# plugV9.net
KiCad netlist of a schematic drawn in EAGLE
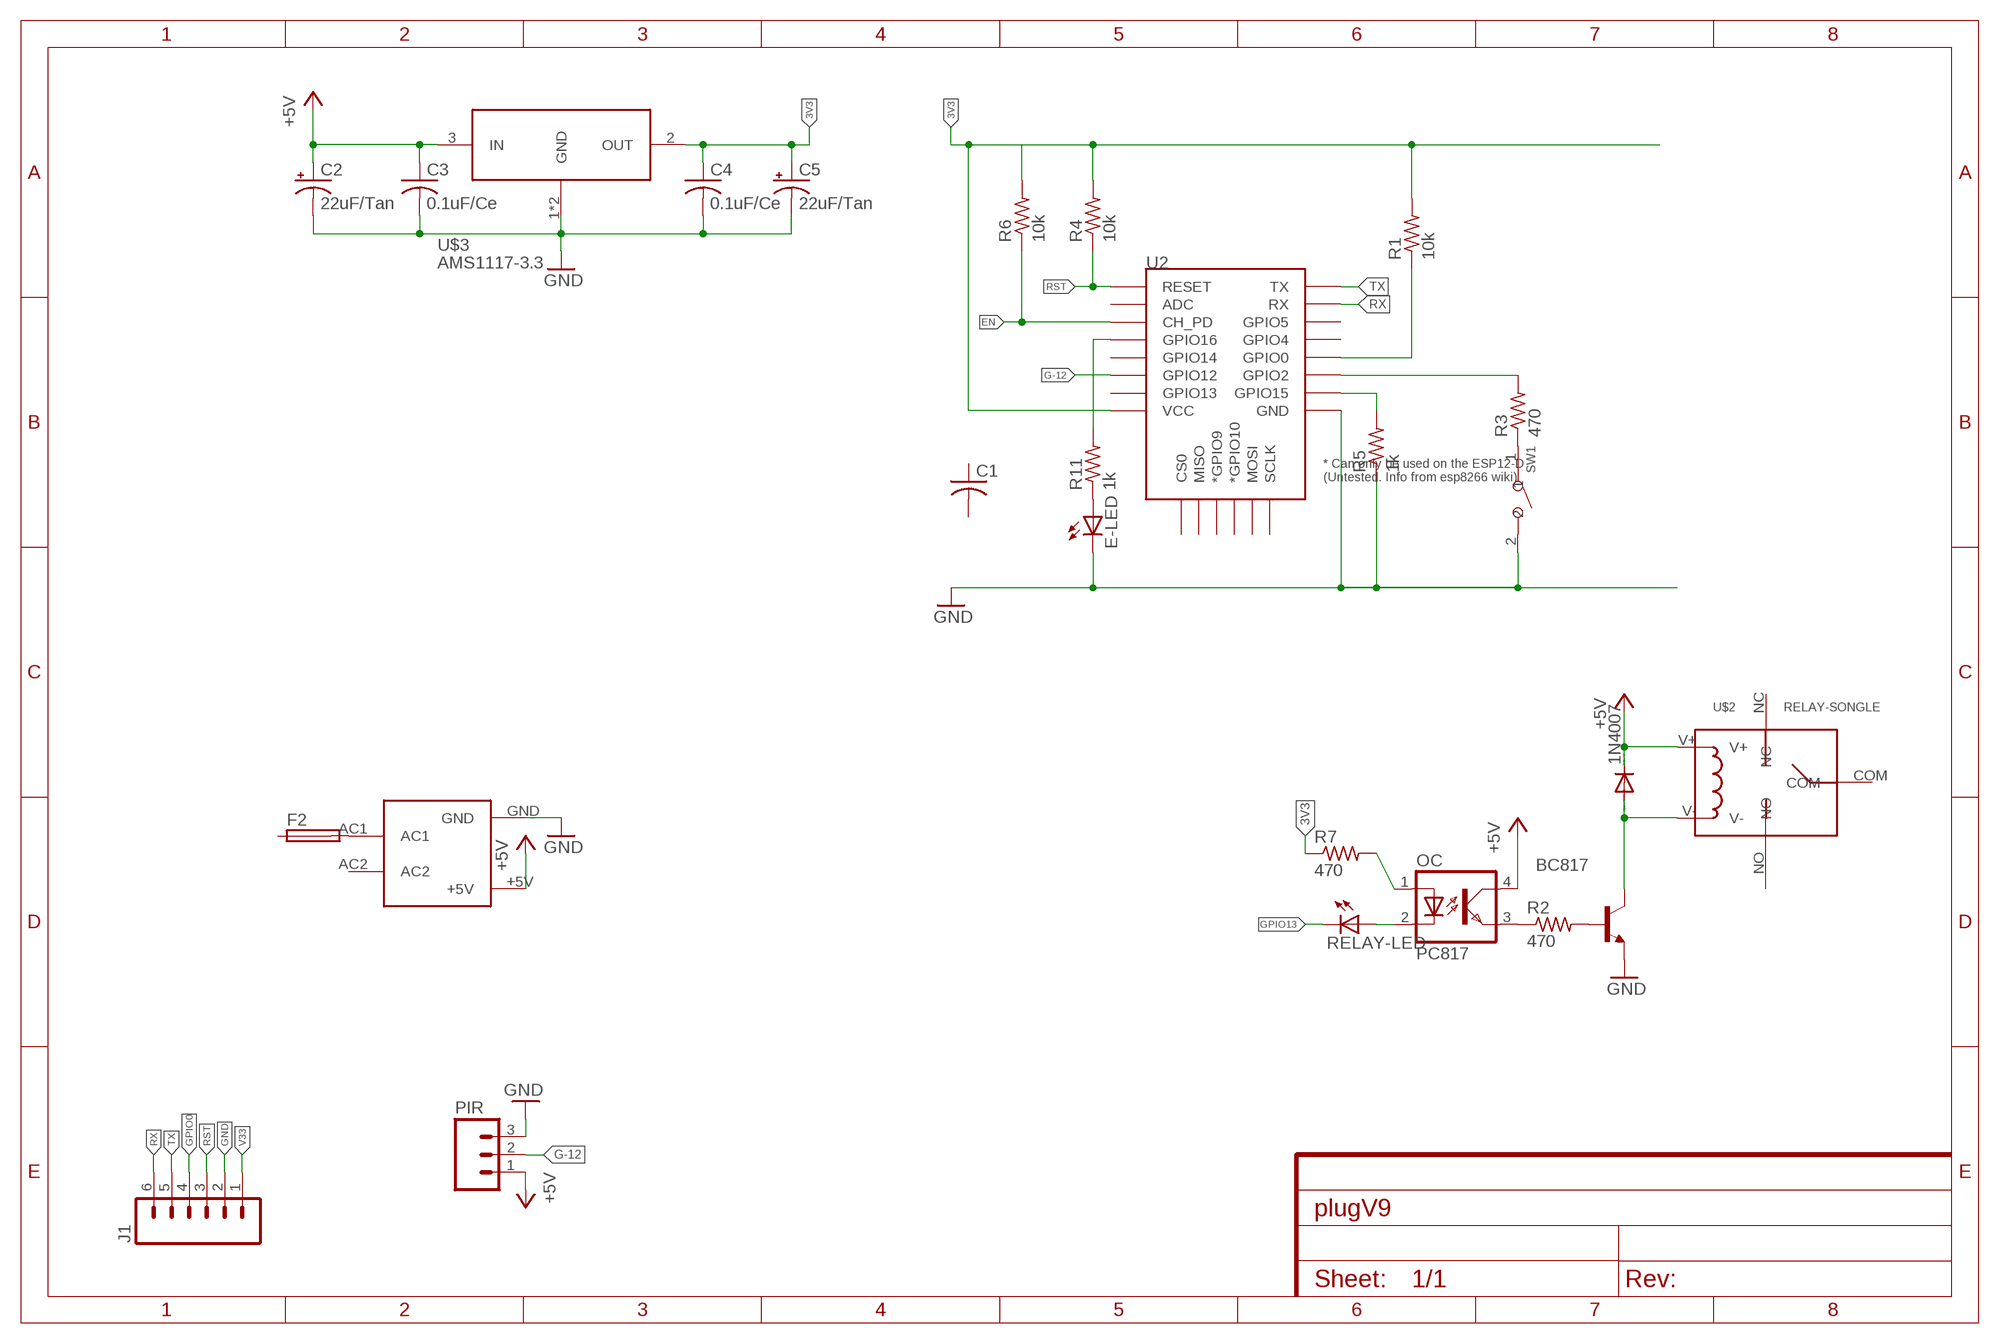
[diagram p0: schematic, sheet 1]

(export (version "E")
  (design (tool "Eeschema 10.0.6"))
  (components
    (comp (ref "1N4007")
      (value "CGRM4007-G")
      (footprint "eagle-import:SOD-123_MINI-SMA")
      (libsource (lib "eagle-import") (part "CGRM400-G7"))
    )
    (comp (ref "BC817")
      (value "BC817-NPN-SOT23-BEC")
      (footprint "eagle-import:SOT23-BEC")
      (libsource (lib "eagle-import") (part "-NPN-SOT23-BECBC817"))
    )
    (comp (ref "C1")
      (value "C-USC0805K")
      (footprint "eagle-import:C0805K")
      (libsource (lib "eagle-import") (part "C-USC0805K"))
    )
    (comp (ref "C2")
      (value "22uF/Tan")
      (footprint "eagle-import:CT3216")
      (libsource (lib "eagle-import") (part "CPOL-USCT3216"))
    )
    (comp (ref "C3")
      (value "0.1uF/Ce")
      (footprint "eagle-import:C0805")
      (libsource (lib "eagle-import") (part "C-USC0805"))
    )
    (comp (ref "C4")
      (value "0.1uF/Ce")
      (footprint "eagle-import:C0805")
      (libsource (lib "eagle-import") (part "C-USC0805"))
    )
    (comp (ref "C5")
      (value "22uF/Tan")
      (footprint "eagle-import:CT3216")
      (libsource (lib "eagle-import") (part "CPOL-USCT3216"))
    )
    (comp (ref "E-LED")
      (value "LEDSML0805")
      (footprint "eagle-import:SML0805")
      (libsource (lib "eagle-import") (part "LEDSML0805"))
    )
    (comp (ref "F2")
      (value "TR5")
      (footprint "eagle-import:TR5")
      (libsource (lib "eagle-import") (part "TR5"))
    )
    (comp (ref "J1")
      (value "M06SILK_FEMALE_PTH")
      (footprint "eagle-import:1X06")
      (libsource (lib "eagle-import") (part "M06SILK_FEMALE_PTH"))
    )
    (comp (ref "OC")
      (value "PC817")
      (footprint "eagle-import:DIL04")
      (fields (field (name "MPN") "PC817X4J000F"))
      (libsource (lib "eagle-import") (part "PC817"))
    )
    (comp (ref "PIR")
      (value "M03POLAR")
      (footprint "eagle-import:MOLEX-1X3")
      (libsource (lib "eagle-import") (part "M03POLAR"))
    )
    (comp (ref "R1")
      (value "10k")
      (footprint "eagle-import:R0805")
      (libsource (lib "eagle-import") (part "R-US_R0805"))
    )
    (comp (ref "R2")
      (value "470")
      (footprint "eagle-import:0204V")
      (libsource (lib "eagle-import") (part "R-US_0204/2V"))
    )
    (comp (ref "R3")
      (value "470")
      (footprint "eagle-import:0204V")
      (libsource (lib "eagle-import") (part "R-US_0204/2V"))
    )
    (comp (ref "R4")
      (value "10k")
      (footprint "eagle-import:R0805")
      (libsource (lib "eagle-import") (part "R-US_R0805"))
    )
    (comp (ref "R5")
      (value "1k")
      (footprint "eagle-import:R0805")
      (libsource (lib "eagle-import") (part "R-US_R0805"))
    )
    (comp (ref "R6")
      (value "10k")
      (footprint "eagle-import:R0805")
      (libsource (lib "eagle-import") (part "R-US_R0805"))
    )
    (comp (ref "R7")
      (value "470")
      (footprint "eagle-import:0204V")
      (libsource (lib "eagle-import") (part "R-US_0204/2V"))
    )
    (comp (ref "R11")
      (value "1k")
      (footprint "eagle-import:R0805")
      (libsource (lib "eagle-import") (part "R-US_R0805"))
    )
    (comp (ref "RELAY-LED")
      (value "LED3MM")
      (footprint "eagle-import:LED3MM")
      (libsource (lib "eagle-import") (part "LED3MM"))
    )
    (comp (ref "SW1")
      (value "DIP-BUTTON(2P-6.0X3.0X4.3MM)-TS-1101F")
      (footprint "eagle-import:SW2-5.0-6.0X3.0X4.3MM")
      (libsource (lib "eagle-import") (part "DIP-BUTTON(2P-6.0X3.0X4.3MM)-TS-1101F"))
    )
    (comp (ref "U$1")
      (value "HLK-PM01")
      (footprint "eagle-import:HLK-PM01")
      (libsource (lib "eagle-import") (part "HLK-PM01"))
    )
    (comp (ref "U$2")
      (value "RELAY-SONGLE")
      (footprint "eagle-import:RELAY-SONGLE")
      (libsource (lib "eagle-import") (part "RELAY-SONGLE"))
    )
    (comp (ref "U$3")
      (value "AMS1117-3.3")
      (footprint "eagle-import:SOT-223")
      (libsource (lib "eagle-import") (part "AMS1117-3.3"))
    )
    (comp (ref "U2")
      (value "ESP12ESMD")
      (footprint "eagle-import:ESP12E-SMD")
      (libsource (lib "eagle-import") (part "ESP12ESMD"))
    )
  )
  (nets
    (net (code "1") (name "+5V") (class "Default")
      (node (ref "1N4007") (pin "C") (pinfunction "C_C") (pintype "passive"))
      (node (ref "C2") (pin "+") (pinfunction "+_+") (pintype "passive"))
      (node (ref "C3") (pin "1") (pinfunction "1_1") (pintype "passive"))
      (node (ref "OC") (pin "4") (pinfunction "COL_4") (pintype "passive"))
      (node (ref "PIR") (pin "1") (pinfunction "1_1") (pintype "passive"))
      (node (ref "U$1") (pin "+5V") (pinfunction "+5V_+5V") (pintype "bidirectional"))
      (node (ref "U$2") (pin "V+") (pinfunction "V+_V+") (pintype "bidirectional"))
      (node (ref "U$3") (pin "3") (pinfunction "IN_3") (pintype "input"))
    )
    (net (code "2") (name "3V3") (class "Default")
      (node (ref "C4") (pin "1") (pinfunction "1_1") (pintype "passive"))
      (node (ref "C5") (pin "+") (pinfunction "+_+") (pintype "passive"))
      (node (ref "R1") (pin "2") (pinfunction "2_2") (pintype "passive"))
      (node (ref "R4") (pin "2") (pinfunction "2_2") (pintype "passive"))
      (node (ref "R7") (pin "1") (pinfunction "1_1") (pintype "passive"))
      (node (ref "U$3") (pin "2") (pinfunction "OUT_2") (pintype "output"))
      (node (ref "U2") (pin "VCC") (pinfunction "VCC_VCC") (pintype "bidirectional"))
    )
    (net (code "3") (name "EN") (class "Default")
      (node (ref "R6") (pin "1") (pinfunction "1_1") (pintype "passive"))
      (node (ref "U2") (pin "CH_PD") (pinfunction "CH_PD_CH_PD") (pintype "bidirectional"))
    )
    (net (code "4") (name "G-12") (class "Default")
      (node (ref "PIR") (pin "2") (pinfunction "2_2") (pintype "passive"))
      (node (ref "U2") (pin "GPIO12") (pinfunction "GPIO12_GPIO12") (pintype "bidirectional"))
    )
    (net (code "5") (name "GND") (class "Default")
      (node (ref "BC817") (pin "E") (pinfunction "E_E") (pintype "passive"))
      (node (ref "C2") (pin "-") (pinfunction "-_-") (pintype "passive"))
      (node (ref "C3") (pin "2") (pinfunction "2_2") (pintype "passive"))
      (node (ref "C4") (pin "2") (pinfunction "2_2") (pintype "passive"))
      (node (ref "C5") (pin "-") (pinfunction "-_-") (pintype "passive"))
      (node (ref "E-LED") (pin "C") (pinfunction "C_C") (pintype "passive"))
      (node (ref "J1") (pin "2") (pinfunction "2_2") (pintype "passive"))
      (node (ref "PIR") (pin "3") (pinfunction "3_3") (pintype "passive"))
      (node (ref "R5") (pin "1") (pinfunction "1_1") (pintype "passive"))
      (node (ref "SW1") (pin "2") (pinfunction "2_2") (pintype "bidirectional"))
      (node (ref "U$1") (pin "GND") (pinfunction "GND_GND") (pintype "bidirectional"))
      (node (ref "U$3") (pin "1") (pinfunction "GND_1") (pintype "passive"))
      (node (ref "U$3") (pin "4") (pinfunction "GND_4") (pintype "passive"))
      (node (ref "U2") (pin "GND") (pinfunction "GND_GND") (pintype "bidirectional"))
    )
    (net (code "6") (name "GPIO0") (class "Default")
      (node (ref "J1") (pin "4") (pinfunction "4_4") (pintype "passive"))
    )
    (net (code "7") (name "GPIO13") (class "Default")
      (node (ref "RELAY-LED") (pin "K") (pinfunction "C_K") (pintype "passive"))
    )
    (net (code "8") (name "Net-(1N4007-PadA)") (class "Default")
      (node (ref "1N4007") (pin "A") (pinfunction "A_A") (pintype "passive"))
      (node (ref "BC817") (pin "C") (pinfunction "C_C") (pintype "passive"))
      (node (ref "U$2") (pin "V-") (pinfunction "V-_V-") (pintype "bidirectional"))
    )
    (net (code "9") (name "Net-(BC817-PadB)") (class "Default")
      (node (ref "BC817") (pin "B") (pinfunction "B_B") (pintype "passive"))
      (node (ref "R2") (pin "2") (pinfunction "2_2") (pintype "passive"))
    )
    (net (code "10") (name "Net-(E-LED-PadA)") (class "Default")
      (node (ref "E-LED") (pin "A") (pinfunction "A_A") (pintype "passive"))
      (node (ref "R11") (pin "1") (pinfunction "1_1") (pintype "passive"))
    )
    (net (code "11") (name "Net-(F2-Pad2)") (class "Default")
      (node (ref "F2") (pin "2") (pinfunction "2_2") (pintype "passive"))
      (node (ref "U$1") (pin "AC1") (pinfunction "AC1_AC1") (pintype "bidirectional"))
    )
    (net (code "12") (name "Net-(OC-A)") (class "Default")
      (node (ref "OC") (pin "1") (pinfunction "A_1") (pintype "passive"))
      (node (ref "R7") (pin "2") (pinfunction "2_2") (pintype "passive"))
    )
    (net (code "13") (name "Net-(OC-C)") (class "Default")
      (node (ref "OC") (pin "2") (pinfunction "C_2") (pintype "passive"))
      (node (ref "RELAY-LED") (pin "A") (pinfunction "A_A") (pintype "passive"))
    )
    (net (code "14") (name "Net-(OC-EMIT)") (class "Default")
      (node (ref "OC") (pin "3") (pinfunction "EMIT_3") (pintype "passive"))
      (node (ref "R2") (pin "1") (pinfunction "1_1") (pintype "passive"))
    )
    (net (code "15") (name "Net-(R1-Pad1)") (class "Default")
      (node (ref "R1") (pin "1") (pinfunction "1_1") (pintype "passive"))
      (node (ref "U2") (pin "GPIO0") (pinfunction "GPIO0_GPIO0") (pintype "bidirectional"))
    )
    (net (code "16") (name "Net-(R3-Pad1)") (class "Default")
      (node (ref "R3") (pin "1") (pinfunction "1_1") (pintype "passive"))
      (node (ref "SW1") (pin "1") (pinfunction "1_1") (pintype "bidirectional"))
    )
    (net (code "17") (name "Net-(R3-Pad2)") (class "Default")
      (node (ref "R3") (pin "2") (pinfunction "2_2") (pintype "passive"))
      (node (ref "U2") (pin "GPIO2") (pinfunction "GPIO2_GPIO2") (pintype "bidirectional"))
    )
    (net (code "18") (name "Net-(R5-Pad2)") (class "Default")
      (node (ref "R5") (pin "2") (pinfunction "2_2") (pintype "passive"))
      (node (ref "U2") (pin "GPIO15") (pinfunction "GPIO15_GPIO15") (pintype "bidirectional"))
    )
    (net (code "19") (name "Net-(R11-Pad2)") (class "Default")
      (node (ref "R11") (pin "2") (pinfunction "2_2") (pintype "passive"))
      (node (ref "U2") (pin "GPIO16") (pinfunction "GPIO16_GPIO16") (pintype "bidirectional"))
    )
    (net (code "20") (name "RST") (class "Default")
      (node (ref "J1") (pin "3") (pinfunction "3_3") (pintype "passive"))
      (node (ref "R4") (pin "1") (pinfunction "1_1") (pintype "passive"))
      (node (ref "U2") (pin "RESET") (pinfunction "RESET_RESET") (pintype "bidirectional"))
    )
    (net (code "21") (name "RX") (class "Default")
      (node (ref "J1") (pin "6") (pinfunction "6_6") (pintype "passive"))
      (node (ref "U2") (pin "RXD0") (pinfunction "RX_RXD0") (pintype "bidirectional"))
    )
    (net (code "22") (name "TX") (class "Default")
      (node (ref "J1") (pin "5") (pinfunction "5_5") (pintype "passive"))
      (node (ref "U2") (pin "TXD0") (pinfunction "TX_TXD0") (pintype "bidirectional"))
    )
    (net (code "23") (name "V33") (class "Default")
      (node (ref "J1") (pin "1") (pinfunction "1_1") (pintype "passive"))
    )
    (net (code "24") (name "unconnected-(C1-Pad1)") (class "Default")
      (node (ref "C1") (pin "1") (pinfunction "1_1") (pintype "passive"))
    )
    (net (code "25") (name "unconnected-(C1-Pad2)") (class "Default")
      (node (ref "C1") (pin "2") (pinfunction "2_2") (pintype "passive"))
    )
    (net (code "26") (name "unconnected-(F2-Pad1)") (class "Default")
      (node (ref "F2") (pin "1") (pinfunction "1_1") (pintype "passive"))
    )
    (net (code "27") (name "unconnected-(R6-Pad2)") (class "Default")
      (node (ref "R6") (pin "2") (pinfunction "2_2") (pintype "passive"))
    )
    (net (code "28") (name "unconnected-(U$1-PadAC2)") (class "Default")
      (node (ref "U$1") (pin "AC2") (pinfunction "AC2_AC2") (pintype "bidirectional"))
    )
    (net (code "29") (name "unconnected-(U$2-PadCOM)") (class "Default")
      (node (ref "U$2") (pin "COM") (pinfunction "COM_COM") (pintype "bidirectional"))
    )
    (net (code "30") (name "unconnected-(U$2-PadNC)") (class "Default")
      (node (ref "U$2") (pin "NC") (pinfunction "NC_NC") (pintype "bidirectional"))
    )
    (net (code "31") (name "unconnected-(U$2-PadNO)") (class "Default")
      (node (ref "U$2") (pin "NO") (pinfunction "NO_NO") (pintype "bidirectional"))
    )
    (net (code "32") (name "unconnected-(U2-*GPIO9-PadGPIO9)") (class "Default")
      (node (ref "U2") (pin "GPIO9") (pinfunction "*GPIO9_GPIO9") (pintype "bidirectional"))
    )
    (net (code "33") (name "unconnected-(U2-*GPIO10-PadGPIO10)") (class "Default")
      (node (ref "U2") (pin "GPIO10") (pinfunction "*GPIO10_GPIO10") (pintype "bidirectional"))
    )
    (net (code "34") (name "unconnected-(U2-PadADC)") (class "Default")
      (node (ref "U2") (pin "ADC") (pinfunction "ADC_ADC") (pintype "bidirectional"))
    )
    (net (code "35") (name "unconnected-(U2-PadCS0)") (class "Default")
      (node (ref "U2") (pin "CS0") (pinfunction "CS0_CS0") (pintype "bidirectional"))
    )
    (net (code "36") (name "unconnected-(U2-PadGPIO4)") (class "Default")
      (node (ref "U2") (pin "GPIO4") (pinfunction "GPIO4_GPIO4") (pintype "bidirectional"))
    )
    (net (code "37") (name "unconnected-(U2-PadGPIO5)") (class "Default")
      (node (ref "U2") (pin "GPIO5") (pinfunction "GPIO5_GPIO5") (pintype "bidirectional"))
    )
    (net (code "38") (name "unconnected-(U2-PadGPIO13)") (class "Default")
      (node (ref "U2") (pin "GPIO13") (pinfunction "GPIO13_GPIO13") (pintype "bidirectional"))
    )
    (net (code "39") (name "unconnected-(U2-PadGPIO14)") (class "Default")
      (node (ref "U2") (pin "GPIO14") (pinfunction "GPIO14_GPIO14") (pintype "bidirectional"))
    )
    (net (code "40") (name "unconnected-(U2-PadMISO)") (class "Default")
      (node (ref "U2") (pin "MISO") (pinfunction "MISO_MISO") (pintype "bidirectional"))
    )
    (net (code "41") (name "unconnected-(U2-PadMOSI)") (class "Default")
      (node (ref "U2") (pin "MOSI") (pinfunction "MOSI_MOSI") (pintype "bidirectional"))
    )
    (net (code "42") (name "unconnected-(U2-PadSCLK)") (class "Default")
      (node (ref "U2") (pin "SCLK") (pinfunction "SCLK_SCLK") (pintype "bidirectional"))
    )
  )
)
